# Main.net
KiCad netlist of a schematic drawn in Altium Designer
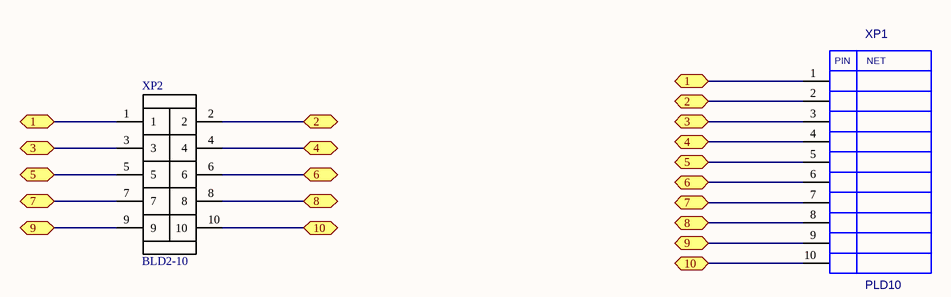
[diagram p0: Main.SchDoc]

(export (version "E")
  (design (tool "Eeschema 10.0.6"))
  (components
    (comp (ref "XP1") (value "PLD10") (footprint "PIN10M") (libsource (lib "gprs_modem_2") (part "PLD10")))
    (comp (ref "XP2")
      (value "BLD2-10")
      (footprint "PLD2-10")
      (libsource (lib "gprs_modem_2") (part "PLD2-10"))
    )
  )
  (nets
    (net (code "1") (name "/1") (class "Default")
      (node (ref "XP1") (pin "1") (pinfunction "1_1") (pintype "passive"))
      (node (ref "XP2") (pin "1") (pinfunction "1_1") (pintype "passive"))
    )
    (net (code "2") (name "/2") (class "Default")
      (node (ref "XP1") (pin "2") (pinfunction "2_2") (pintype "passive"))
      (node (ref "XP2") (pin "2") (pinfunction "2_2") (pintype "passive"))
    )
    (net (code "3") (name "/3") (class "Default")
      (node (ref "XP1") (pin "3") (pinfunction "3_3") (pintype "passive"))
      (node (ref "XP2") (pin "3") (pinfunction "3_3") (pintype "passive"))
    )
    (net (code "4") (name "/4") (class "Default")
      (node (ref "XP1") (pin "4") (pinfunction "4_4") (pintype "passive"))
      (node (ref "XP2") (pin "4") (pinfunction "4_4") (pintype "passive"))
    )
    (net (code "5") (name "/5") (class "Default")
      (node (ref "XP1") (pin "5") (pinfunction "5_5") (pintype "passive"))
      (node (ref "XP2") (pin "5") (pinfunction "5_5") (pintype "passive"))
    )
    (net (code "6") (name "/6") (class "Default")
      (node (ref "XP1") (pin "6") (pinfunction "6_6") (pintype "passive"))
      (node (ref "XP2") (pin "6") (pinfunction "6_6") (pintype "passive"))
    )
    (net (code "7") (name "/7") (class "Default")
      (node (ref "XP1") (pin "7") (pinfunction "7_7") (pintype "passive"))
      (node (ref "XP2") (pin "7") (pinfunction "7_7") (pintype "passive"))
    )
    (net (code "8") (name "/8") (class "Default")
      (node (ref "XP1") (pin "8") (pinfunction "8_8") (pintype "passive"))
      (node (ref "XP2") (pin "8") (pinfunction "8_8") (pintype "passive"))
    )
    (net (code "9") (name "/9") (class "Default")
      (node (ref "XP1") (pin "9") (pinfunction "9_9") (pintype "passive"))
      (node (ref "XP2") (pin "9") (pinfunction "9_9") (pintype "passive"))
    )
    (net (code "10") (name "/10") (class "Default")
      (node (ref "XP1") (pin "10") (pinfunction "10_10") (pintype "passive"))
      (node (ref "XP2") (pin "10") (pinfunction "10_10") (pintype "passive"))
    )
  )
)
